# rx.net
KiCad netlist of a schematic drawn in EAGLE
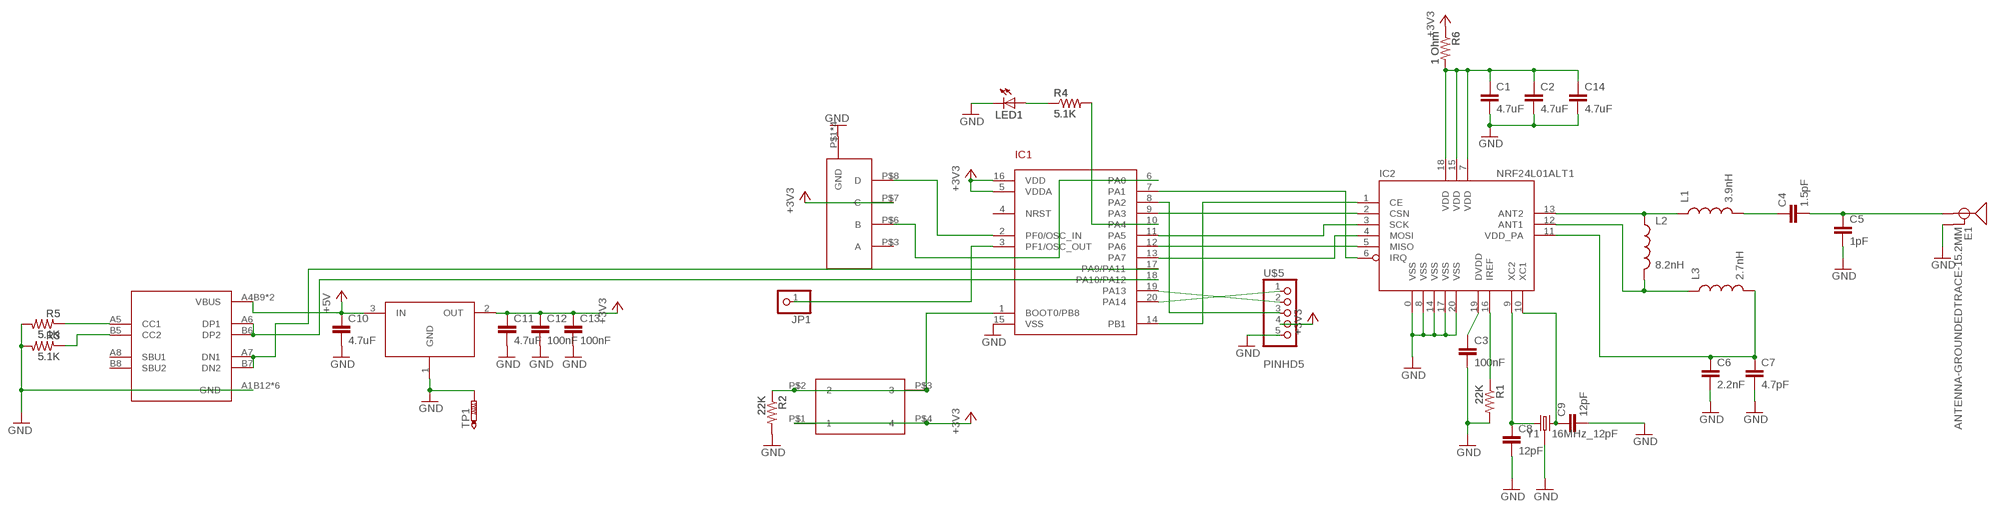
[diagram p0: schematic, sheet 1]

(export (version "E")
  (design (tool "Eeschema 10.0.6"))
  (components
    (comp (ref "C1")
      (value "4.7uF")
      (footprint "eagle-import:0805")
      (libsource (lib "eagle-import") (part "CAP0805"))
    )
    (comp (ref "C2")
      (value "4.7uF")
      (footprint "eagle-import:0805")
      (libsource (lib "eagle-import") (part "CAP0805"))
    )
    (comp (ref "C3")
      (value "100nF")
      (footprint "eagle-import:0805")
      (libsource (lib "eagle-import") (part "CAP0805"))
    )
    (comp (ref "C4")
      (value "1.5pF")
      (footprint "eagle-import:0805")
      (libsource (lib "eagle-import") (part "CAP0805"))
    )
    (comp (ref "C5")
      (value "1pF")
      (footprint "eagle-import:0805")
      (libsource (lib "eagle-import") (part "CAP0805"))
    )
    (comp (ref "C6")
      (value "2.2nF")
      (footprint "eagle-import:0805")
      (libsource (lib "eagle-import") (part "CAP0805"))
    )
    (comp (ref "C7")
      (value "4.7pF")
      (footprint "eagle-import:0805")
      (libsource (lib "eagle-import") (part "CAP0805"))
    )
    (comp (ref "C8")
      (value "12pF")
      (footprint "eagle-import:0805")
      (libsource (lib "eagle-import") (part "CAP0805"))
    )
    (comp (ref "C9")
      (value "12pF")
      (footprint "eagle-import:0805")
      (libsource (lib "eagle-import") (part "CAP0805"))
    )
    (comp (ref "C10")
      (value "4.7uF")
      (footprint "eagle-import:0805")
      (libsource (lib "eagle-import") (part "CAP0805"))
    )
    (comp (ref "C11")
      (value "4.7uF")
      (footprint "eagle-import:0805")
      (libsource (lib "eagle-import") (part "CAP0805"))
    )
    (comp (ref "C12")
      (value "100nF")
      (footprint "eagle-import:0805")
      (libsource (lib "eagle-import") (part "CAP0805"))
    )
    (comp (ref "C13")
      (value "100nF")
      (footprint "eagle-import:0805")
      (libsource (lib "eagle-import") (part "CAP0805"))
    )
    (comp (ref "C14")
      (value "4.7uF")
      (footprint "eagle-import:0805")
      (libsource (lib "eagle-import") (part "CAP0805"))
    )
    (comp (ref "E1")
      (value "ANTENNA-GROUNDEDTRACE-15.2MM")
      (footprint "eagle-import:TRACE_ANTENNA_2.4GHZ_15.2MM")
      (libsource (lib "eagle-import") (part "ANTENNA-GROUNDEDTRACE-15.2MM"))
    )
    (comp (ref "IC1")
      (value "STM32F042F4")
      (footprint "eagle-import:TSSOP20")
      (libsource (lib "eagle-import") (part "STM32F042F4"))
    )
    (comp (ref "IC2")
      (value "NRF24L01ALT1")
      (footprint "eagle-import:QFN20_ALT1")
      (libsource (lib "eagle-import") (part "NRF24L01ALT1"))
    )
    (comp (ref "JP1")
      (value "PINHD-1X1CB")
      (footprint "eagle-import:1X01-CLEANBIG")
      (libsource (lib "eagle-import") (part "PINHD-1X1CB"))
    )
    (comp (ref "L1")
      (value "3.9nH")
      (footprint "eagle-import:0805")
      (libsource (lib "eagle-import") (part "INDUCTOR0805"))
    )
    (comp (ref "L2")
      (value "8.2nH")
      (footprint "eagle-import:0805")
      (libsource (lib "eagle-import") (part "INDUCTOR0805"))
    )
    (comp (ref "L3")
      (value "2.7nH")
      (footprint "eagle-import:0805")
      (libsource (lib "eagle-import") (part "INDUCTOR0805"))
    )
    (comp (ref "LED1")
      (value "LEDCHIP-LED0805")
      (footprint "eagle-import:CHIP-LED0805")
      (libsource (lib "eagle-import") (part "LEDCHIP-LED0805"))
    )
    (comp (ref "R1")
      (value "22K")
      (footprint "eagle-import:0805")
      (libsource (lib "eagle-import") (part "RESISTOR0805-RES"))
    )
    (comp (ref "R2")
      (value "22K")
      (footprint "eagle-import:0805")
      (libsource (lib "eagle-import") (part "RESISTOR0805-RES"))
    )
    (comp (ref "R3")
      (value "5.1K")
      (footprint "eagle-import:0805")
      (libsource (lib "eagle-import") (part "RESISTOR0805-RES"))
    )
    (comp (ref "R4")
      (value "5.1K")
      (footprint "eagle-import:0805")
      (libsource (lib "eagle-import") (part "RESISTOR0805-RES"))
    )
    (comp (ref "R5")
      (value "5.1K")
      (footprint "eagle-import:0805")
      (libsource (lib "eagle-import") (part "RESISTOR0805-RES"))
    )
    (comp (ref "R6")
      (value "1 Ohm")
      (footprint "eagle-import:0805")
      (libsource (lib "eagle-import") (part "RESISTOR0805-RES"))
    )
    (comp (ref "SW1")
      (value "SW_3POS_DEVSW_3POS_OFFICIAL")
      (footprint "eagle-import:SW_3POS_FOOT_OFFICIAL")
      (libsource (lib "eagle-import") (part "SW_3POS_DEVSW_3POS_OFFICIAL"))
    )
    (comp (ref "SW2")
      (value "324_SW324_SWITCH_FOOT_HOLE")
      (footprint "eagle-import:342_SWICH_FOOT_HOLE")
      (libsource (lib "eagle-import") (part "324_SW324_SWITCH_FOOT_HOLE"))
    )
    (comp (ref "TP1")
      (value "PTR1TP18R")
      (footprint "eagle-import:TP18R")
      (libsource (lib "eagle-import") (part "PTR1TP18R"))
    )
    (comp (ref "U$5")
      (value "PINHD5")
      (footprint "eagle-import:1X05")
      (libsource (lib "eagle-import") (part "PINHD5"))
    )
    (comp (ref "U1")
      (value "USBC_16P")
      (footprint "eagle-import:USBC_16P_FOOT")
      (libsource (lib "eagle-import") (part "USBC_16P"))
    )
    (comp (ref "U2")
      (value "XC6206_DEV")
      (footprint "eagle-import:SOT23R_INFINEON")
      (libsource (lib "eagle-import") (part "XC6206_DEV"))
    )
    (comp (ref "Y1")
      (value "16MHz_12pF")
      (footprint "eagle-import:CRYSTAL-SMD-3.2X2.5MM")
      (libsource (lib "eagle-import") (part "CRYSTAL-26MHZSMD-3.2X2.5"))
    )
  )
  (nets
    (net (code "1") (name "+3V3") (class "Default")
      (node (ref "C11") (pin "1") (pinfunction "1_1") (pintype "passive"))
      (node (ref "C12") (pin "1") (pinfunction "1_1") (pintype "passive"))
      (node (ref "C13") (pin "1") (pinfunction "1_1") (pintype "passive"))
      (node (ref "IC1") (pin "16") (pinfunction "VDD_16") (pintype "bidirectional"))
      (node (ref "IC1") (pin "5") (pinfunction "VDDA_5") (pintype "bidirectional"))
      (node (ref "R6") (pin "1") (pinfunction "1_1") (pintype "passive"))
      (node (ref "SW1") (pin "P$7") (pinfunction "C_P$7") (pintype "bidirectional"))
      (node (ref "SW2") (pin "P$1") (pinfunction "1_P$1") (pintype "bidirectional"))
      (node (ref "SW2") (pin "P$4") (pinfunction "4_P$4") (pintype "bidirectional"))
      (node (ref "U$5") (pin "4") (pinfunction "4_4") (pintype "passive"))
      (node (ref "U2") (pin "2") (pinfunction "OUT_2") (pintype "bidirectional"))
    )
    (net (code "2") (name "+5V") (class "Default")
      (node (ref "C10") (pin "1") (pinfunction "1_1") (pintype "passive"))
      (node (ref "U1") (pin "A4B9") (pinfunction "VBUS_A4B9") (pintype "bidirectional"))
      (node (ref "U1") (pin "B4A9") (pinfunction "VBUS_B4A9") (pintype "bidirectional"))
      (node (ref "U2") (pin "3") (pinfunction "IN_3") (pintype "bidirectional"))
    )
    (net (code "3") (name "GND") (class "Default")
      (node (ref "C1") (pin "2") (pinfunction "2_2") (pintype "passive"))
      (node (ref "C10") (pin "2") (pinfunction "2_2") (pintype "passive"))
      (node (ref "C11") (pin "2") (pinfunction "2_2") (pintype "passive"))
      (node (ref "C12") (pin "2") (pinfunction "2_2") (pintype "passive"))
      (node (ref "C13") (pin "2") (pinfunction "2_2") (pintype "passive"))
      (node (ref "C14") (pin "2") (pinfunction "2_2") (pintype "passive"))
      (node (ref "C2") (pin "2") (pinfunction "2_2") (pintype "passive"))
      (node (ref "C3") (pin "2") (pinfunction "2_2") (pintype "passive"))
      (node (ref "C5") (pin "2") (pinfunction "2_2") (pintype "passive"))
      (node (ref "C6") (pin "2") (pinfunction "2_2") (pintype "passive"))
      (node (ref "C7") (pin "2") (pinfunction "2_2") (pintype "passive"))
      (node (ref "C8") (pin "2") (pinfunction "2_2") (pintype "passive"))
      (node (ref "C9") (pin "2") (pinfunction "2_2") (pintype "passive"))
      (node (ref "E1") (pin "GND") (pinfunction "GND_GND") (pintype "bidirectional"))
      (node (ref "IC1") (pin "15") (pinfunction "VSS_15") (pintype "bidirectional"))
      (node (ref "IC2") (pin "0") (pinfunction "VSS_0") (pintype "power_in"))
      (node (ref "IC2") (pin "14") (pinfunction "VSS_14") (pintype "power_in"))
      (node (ref "IC2") (pin "17") (pinfunction "VSS_17") (pintype "power_in"))
      (node (ref "IC2") (pin "20") (pinfunction "VSS_20") (pintype "power_in"))
      (node (ref "IC2") (pin "8") (pinfunction "VSS_8") (pintype "power_in"))
      (node (ref "LED1") (pin "C") (pinfunction "C_C") (pintype "passive"))
      (node (ref "R1") (pin "2") (pinfunction "2_2") (pintype "passive"))
      (node (ref "R2") (pin "2") (pinfunction "2_2") (pintype "passive"))
      (node (ref "R3") (pin "2") (pinfunction "2_2") (pintype "passive"))
      (node (ref "R5") (pin "2") (pinfunction "2_2") (pintype "passive"))
      (node (ref "SW1") (pin "P$1") (pinfunction "GND_P$1") (pintype "bidirectional"))
      (node (ref "SW1") (pin "P$2") (pinfunction "GND_P$2") (pintype "bidirectional"))
      (node (ref "SW1") (pin "P$4") (pinfunction "GND_P$4") (pintype "bidirectional"))
      (node (ref "SW1") (pin "P$5") (pinfunction "GND_P$5") (pintype "bidirectional"))
      (node (ref "TP1") (pin "TP") (pinfunction "TP_TP") (pintype "input"))
      (node (ref "U$5") (pin "5") (pinfunction "5_5") (pintype "passive"))
      (node (ref "U1") (pin "A1B12") (pinfunction "GND_A1B12") (pintype "bidirectional"))
      (node (ref "U1") (pin "B11A12") (pinfunction "GND_B11A12") (pintype "bidirectional"))
      (node (ref "U1") (pin "P$13") (pinfunction "GND_P$13") (pintype "bidirectional"))
      (node (ref "U1") (pin "P$14") (pinfunction "GND_P$14") (pintype "bidirectional"))
      (node (ref "U1") (pin "P$15") (pinfunction "GND_P$15") (pintype "bidirectional"))
      (node (ref "U1") (pin "P$16") (pinfunction "GND_P$16") (pintype "bidirectional"))
      (node (ref "U2") (pin "1") (pinfunction "GND_1") (pintype "bidirectional"))
      (node (ref "Y1") (pin "2") (pinfunction "3_2") (pintype "passive"))
      (node (ref "Y1") (pin "4") (pinfunction "3_4") (pintype "passive"))
    )
    (net (code "4") (name "Net-(C1-Pad1)") (class "Default")
      (node (ref "C1") (pin "1") (pinfunction "1_1") (pintype "passive"))
      (node (ref "C14") (pin "1") (pinfunction "1_1") (pintype "passive"))
      (node (ref "C2") (pin "1") (pinfunction "1_1") (pintype "passive"))
      (node (ref "IC2") (pin "15") (pinfunction "VDD_15") (pintype "power_in"))
      (node (ref "IC2") (pin "18") (pinfunction "VDD_18") (pintype "power_in"))
      (node (ref "IC2") (pin "7") (pinfunction "VDD_7") (pintype "power_in"))
      (node (ref "R6") (pin "2") (pinfunction "2_2") (pintype "passive"))
    )
    (net (code "5") (name "Net-(C4-Pad1)") (class "Default")
      (node (ref "C4") (pin "1") (pinfunction "1_1") (pintype "passive"))
      (node (ref "L1") (pin "2") (pinfunction "2_2") (pintype "passive"))
    )
    (net (code "6") (name "Net-(E1-SIGNAL)") (class "Default")
      (node (ref "C4") (pin "2") (pinfunction "2_2") (pintype "passive"))
      (node (ref "C5") (pin "1") (pinfunction "1_1") (pintype "passive"))
      (node (ref "E1") (pin "ANT") (pinfunction "SIGNAL_ANT") (pintype "bidirectional"))
    )
    (net (code "7") (name "Net-(IC1-BOOT0{slash}PB8)") (class "Default")
      (node (ref "IC1") (pin "1") (pinfunction "BOOT0/PB8_1") (pintype "bidirectional"))
      (node (ref "R2") (pin "1") (pinfunction "1_1") (pintype "passive"))
      (node (ref "SW2") (pin "P$2") (pinfunction "2_P$2") (pintype "bidirectional"))
      (node (ref "SW2") (pin "P$3") (pinfunction "3_P$3") (pintype "bidirectional"))
    )
    (net (code "8") (name "Net-(IC1-PA0)") (class "Default")
      (node (ref "IC1") (pin "6") (pinfunction "PA0_6") (pintype "bidirectional"))
      (node (ref "SW1") (pin "P$6") (pinfunction "B_P$6") (pintype "bidirectional"))
    )
    (net (code "9") (name "Net-(IC1-PA1)") (class "Default")
      (node (ref "IC1") (pin "7") (pinfunction "PA1_7") (pintype "bidirectional"))
      (node (ref "IC2") (pin "6") (pinfunction "IRQ_6") (pintype "output"))
    )
    (net (code "10") (name "Net-(IC1-PA2)") (class "Default")
      (node (ref "IC1") (pin "8") (pinfunction "PA2_8") (pintype "bidirectional"))
      (node (ref "U$5") (pin "3") (pinfunction "3_3") (pintype "passive"))
    )
    (net (code "11") (name "Net-(IC1-PA3)") (class "Default")
      (node (ref "IC1") (pin "9") (pinfunction "PA3_9") (pintype "bidirectional"))
      (node (ref "IC2") (pin "2") (pinfunction "CSN_2") (pintype "input"))
    )
    (net (code "12") (name "Net-(IC1-PA4)") (class "Default")
      (node (ref "IC1") (pin "10") (pinfunction "PA4_10") (pintype "bidirectional"))
      (node (ref "R4") (pin "2") (pinfunction "2_2") (pintype "passive"))
    )
    (net (code "13") (name "Net-(IC1-PA5)") (class "Default")
      (node (ref "IC1") (pin "11") (pinfunction "PA5_11") (pintype "bidirectional"))
      (node (ref "IC2") (pin "3") (pinfunction "SCK_3") (pintype "input"))
    )
    (net (code "14") (name "Net-(IC1-PA6)") (class "Default")
      (node (ref "IC1") (pin "12") (pinfunction "PA6_12") (pintype "bidirectional"))
      (node (ref "IC2") (pin "5") (pinfunction "MISO_5") (pintype "output"))
    )
    (net (code "15") (name "Net-(IC1-PA7)") (class "Default")
      (node (ref "IC1") (pin "13") (pinfunction "PA7_13") (pintype "bidirectional"))
      (node (ref "IC2") (pin "4") (pinfunction "MOSI_4") (pintype "input"))
    )
    (net (code "16") (name "Net-(IC1-PA9{slash}PA11)") (class "Default")
      (node (ref "IC1") (pin "17") (pinfunction "PA9/PA11_17") (pintype "bidirectional"))
      (node (ref "U1") (pin "A7") (pinfunction "DN1_A7") (pintype "bidirectional"))
      (node (ref "U1") (pin "B7") (pinfunction "DN2_B7") (pintype "bidirectional"))
    )
    (net (code "17") (name "Net-(IC1-PA10{slash}PA12)") (class "Default")
      (node (ref "IC1") (pin "18") (pinfunction "PA10/PA12_18") (pintype "bidirectional"))
      (node (ref "U1") (pin "A6") (pinfunction "DP1_A6") (pintype "bidirectional"))
      (node (ref "U1") (pin "B6") (pinfunction "DP2_B6") (pintype "bidirectional"))
    )
    (net (code "18") (name "Net-(IC1-PA13)") (class "Default")
      (node (ref "IC1") (pin "19") (pinfunction "PA13_19") (pintype "bidirectional"))
      (node (ref "U$5") (pin "2") (pinfunction "2_2") (pintype "passive"))
    )
    (net (code "19") (name "Net-(IC1-PA14)") (class "Default")
      (node (ref "IC1") (pin "20") (pinfunction "PA14_20") (pintype "bidirectional"))
      (node (ref "U$5") (pin "1") (pinfunction "1_1") (pintype "passive"))
    )
    (net (code "20") (name "Net-(IC1-PB1)") (class "Default")
      (node (ref "IC1") (pin "14") (pinfunction "PB1_14") (pintype "bidirectional"))
      (node (ref "IC2") (pin "1") (pinfunction "CE_1") (pintype "input"))
    )
    (net (code "21") (name "Net-(IC1-PF0{slash}OSC_IN)") (class "Default")
      (node (ref "IC1") (pin "2") (pinfunction "PF0/OSC_IN_2") (pintype "bidirectional"))
      (node (ref "SW1") (pin "P$8") (pinfunction "D_P$8") (pintype "bidirectional"))
    )
    (net (code "22") (name "Net-(IC1-PF1{slash}OSC_OUT)") (class "Default")
      (node (ref "IC1") (pin "3") (pinfunction "PF1/OSC_OUT_3") (pintype "bidirectional"))
      (node (ref "JP1") (pin "1") (pinfunction "1_1") (pintype "passive"))
    )
    (net (code "23") (name "Net-(IC2-ANT1)") (class "Default")
      (node (ref "IC2") (pin "12") (pinfunction "ANT1_12") (pintype "output"))
      (node (ref "L2") (pin "2") (pinfunction "2_2") (pintype "passive"))
      (node (ref "L3") (pin "1") (pinfunction "1_1") (pintype "passive"))
    )
    (net (code "24") (name "Net-(IC2-ANT2)") (class "Default")
      (node (ref "IC2") (pin "13") (pinfunction "ANT2_13") (pintype "output"))
      (node (ref "L1") (pin "1") (pinfunction "1_1") (pintype "passive"))
      (node (ref "L2") (pin "1") (pinfunction "1_1") (pintype "passive"))
    )
    (net (code "25") (name "Net-(IC2-DVDD)") (class "Default")
      (node (ref "C3") (pin "1") (pinfunction "1_1") (pintype "passive"))
      (node (ref "IC2") (pin "19") (pinfunction "DVDD_19") (pintype "power_in"))
    )
    (net (code "26") (name "Net-(IC2-IREF)") (class "Default")
      (node (ref "IC2") (pin "16") (pinfunction "IREF_16") (pintype "input"))
      (node (ref "R1") (pin "1") (pinfunction "1_1") (pintype "passive"))
    )
    (net (code "27") (name "Net-(IC2-VDD_PA)") (class "Default")
      (node (ref "C6") (pin "1") (pinfunction "1_1") (pintype "passive"))
      (node (ref "C7") (pin "1") (pinfunction "1_1") (pintype "passive"))
      (node (ref "IC2") (pin "11") (pinfunction "VDD_PA_11") (pintype "power_in"))
      (node (ref "L3") (pin "2") (pinfunction "2_2") (pintype "passive"))
    )
    (net (code "28") (name "Net-(IC2-XC1)") (class "Default")
      (node (ref "C9") (pin "1") (pinfunction "1_1") (pintype "passive"))
      (node (ref "IC2") (pin "10") (pinfunction "XC1_10") (pintype "input"))
      (node (ref "Y1") (pin "3") (pinfunction "2_3") (pintype "passive"))
    )
    (net (code "29") (name "Net-(IC2-XC2)") (class "Default")
      (node (ref "C8") (pin "1") (pinfunction "1_1") (pintype "passive"))
      (node (ref "IC2") (pin "9") (pinfunction "XC2_9") (pintype "input"))
      (node (ref "Y1") (pin "1") (pinfunction "1_1") (pintype "passive"))
    )
    (net (code "30") (name "Net-(LED1-PadA)") (class "Default")
      (node (ref "LED1") (pin "A") (pinfunction "A_A") (pintype "passive"))
      (node (ref "R4") (pin "1") (pinfunction "1_1") (pintype "passive"))
    )
    (net (code "31") (name "Net-(U1-CC1)") (class "Default")
      (node (ref "R5") (pin "1") (pinfunction "1_1") (pintype "passive"))
      (node (ref "U1") (pin "A5") (pinfunction "CC1_A5") (pintype "bidirectional"))
    )
    (net (code "32") (name "Net-(U1-CC2)") (class "Default")
      (node (ref "R3") (pin "1") (pinfunction "1_1") (pintype "passive"))
      (node (ref "U1") (pin "B5") (pinfunction "CC2_B5") (pintype "bidirectional"))
    )
    (net (code "33") (name "unconnected-(IC1-NRST-Pad4)") (class "Default")
      (node (ref "IC1") (pin "4") (pinfunction "NRST_4") (pintype "bidirectional"))
    )
    (net (code "34") (name "unconnected-(SW1-A-PadP$3)") (class "Default")
      (node (ref "SW1") (pin "P$3") (pinfunction "A_P$3") (pintype "bidirectional"))
    )
    (net (code "35") (name "unconnected-(U1-SBU1-PadA8)") (class "Default")
      (node (ref "U1") (pin "A8") (pinfunction "SBU1_A8") (pintype "bidirectional"))
    )
    (net (code "36") (name "unconnected-(U1-SBU2-PadB8)") (class "Default")
      (node (ref "U1") (pin "B8") (pinfunction "SBU2_B8") (pintype "bidirectional"))
    )
  )
)
